# INDICATOR.net
KiCad netlist of a schematic drawn in Altium Designer
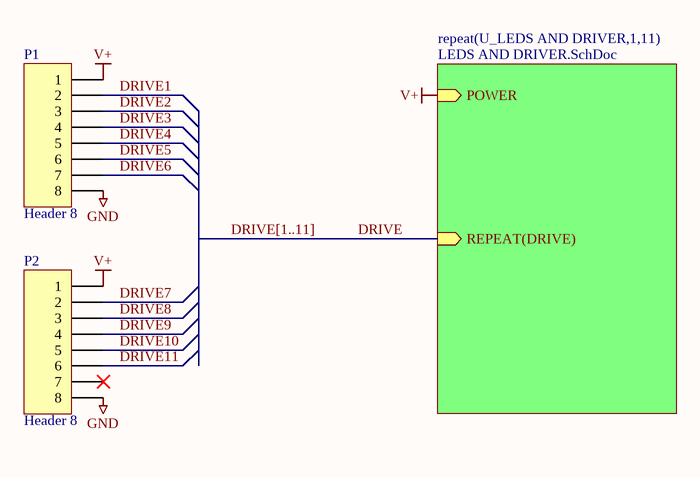
[diagram p0: INDICATOR.SchDoc]

(export (version "E")
  (design (tool "Eeschema 10.0.6"))
  (components
    (comp (ref "P1")
      (value "Header 8")
      (footprint "HDR1X8")
      (description "Header, 8-Pin")
      (fields (field (name "PUBLISHER") "Altium Limited"))
      (libsource (lib "Miscellaneous Connectors") (part "Header 8"))
    )
    (comp (ref "P2")
      (value "Header 8")
      (footprint "HDR1X8")
      (description "Header, 8-Pin")
      (fields (field (name "PUBLISHER") "Altium Limited"))
      (libsource (lib "Miscellaneous Connectors") (part "Header 8"))
    )
  )
  (nets
    (net (code "2") (name "/DRIVE1") (class "Default")
      (node (ref "P1") (pin "2") (pinfunction "2_2") (pintype "passive"))
    )
    (net (code "3") (name "/DRIVE2") (class "Default")
      (node (ref "P1") (pin "3") (pinfunction "3_3") (pintype "passive"))
    )
    (net (code "4") (name "/DRIVE3") (class "Default")
      (node (ref "P1") (pin "4") (pinfunction "4_4") (pintype "passive"))
    )
    (net (code "5") (name "/DRIVE4") (class "Default")
      (node (ref "P1") (pin "5") (pinfunction "5_5") (pintype "passive"))
    )
    (net (code "6") (name "/DRIVE5") (class "Default")
      (node (ref "P1") (pin "6") (pinfunction "6_6") (pintype "passive"))
    )
    (net (code "7") (name "/DRIVE6") (class "Default")
      (node (ref "P1") (pin "7") (pinfunction "7_7") (pintype "passive"))
    )
    (net (code "8") (name "/DRIVE7") (class "Default")
      (node (ref "P2") (pin "2") (pinfunction "2_2") (pintype "passive"))
    )
    (net (code "9") (name "/DRIVE8") (class "Default")
      (node (ref "P2") (pin "3") (pinfunction "3_3") (pintype "passive"))
    )
    (net (code "10") (name "/DRIVE9") (class "Default")
      (node (ref "P2") (pin "4") (pinfunction "4_4") (pintype "passive"))
    )
    (net (code "11") (name "/DRIVE10") (class "Default")
      (node (ref "P2") (pin "5") (pinfunction "5_5") (pintype "passive"))
    )
    (net (code "12") (name "/DRIVE11") (class "Default")
      (node (ref "P2") (pin "6") (pinfunction "6_6") (pintype "passive"))
    )
    (net (code "14") (name "GND") (class "Default")
      (node (ref "P1") (pin "8") (pinfunction "8_8") (pintype "passive"))
      (node (ref "P2") (pin "8") (pinfunction "8_8") (pintype "passive"))
    )
    (net (code "15") (name "V+") (class "Default")
      (node (ref "P1") (pin "1") (pinfunction "1_1") (pintype "passive"))
      (node (ref "P2") (pin "1") (pinfunction "1_1") (pintype "passive"))
    )
    (net (code "16") (name "unconnected-(P2-Pad7)") (class "Default")
      (node (ref "P2") (pin "7") (pinfunction "7_7") (pintype "passive+no_connect"))
    )
  )
)
